# remote_glove_1_0_2021-01-08.net
KiCad netlist of a schematic drawn in EasyEDA
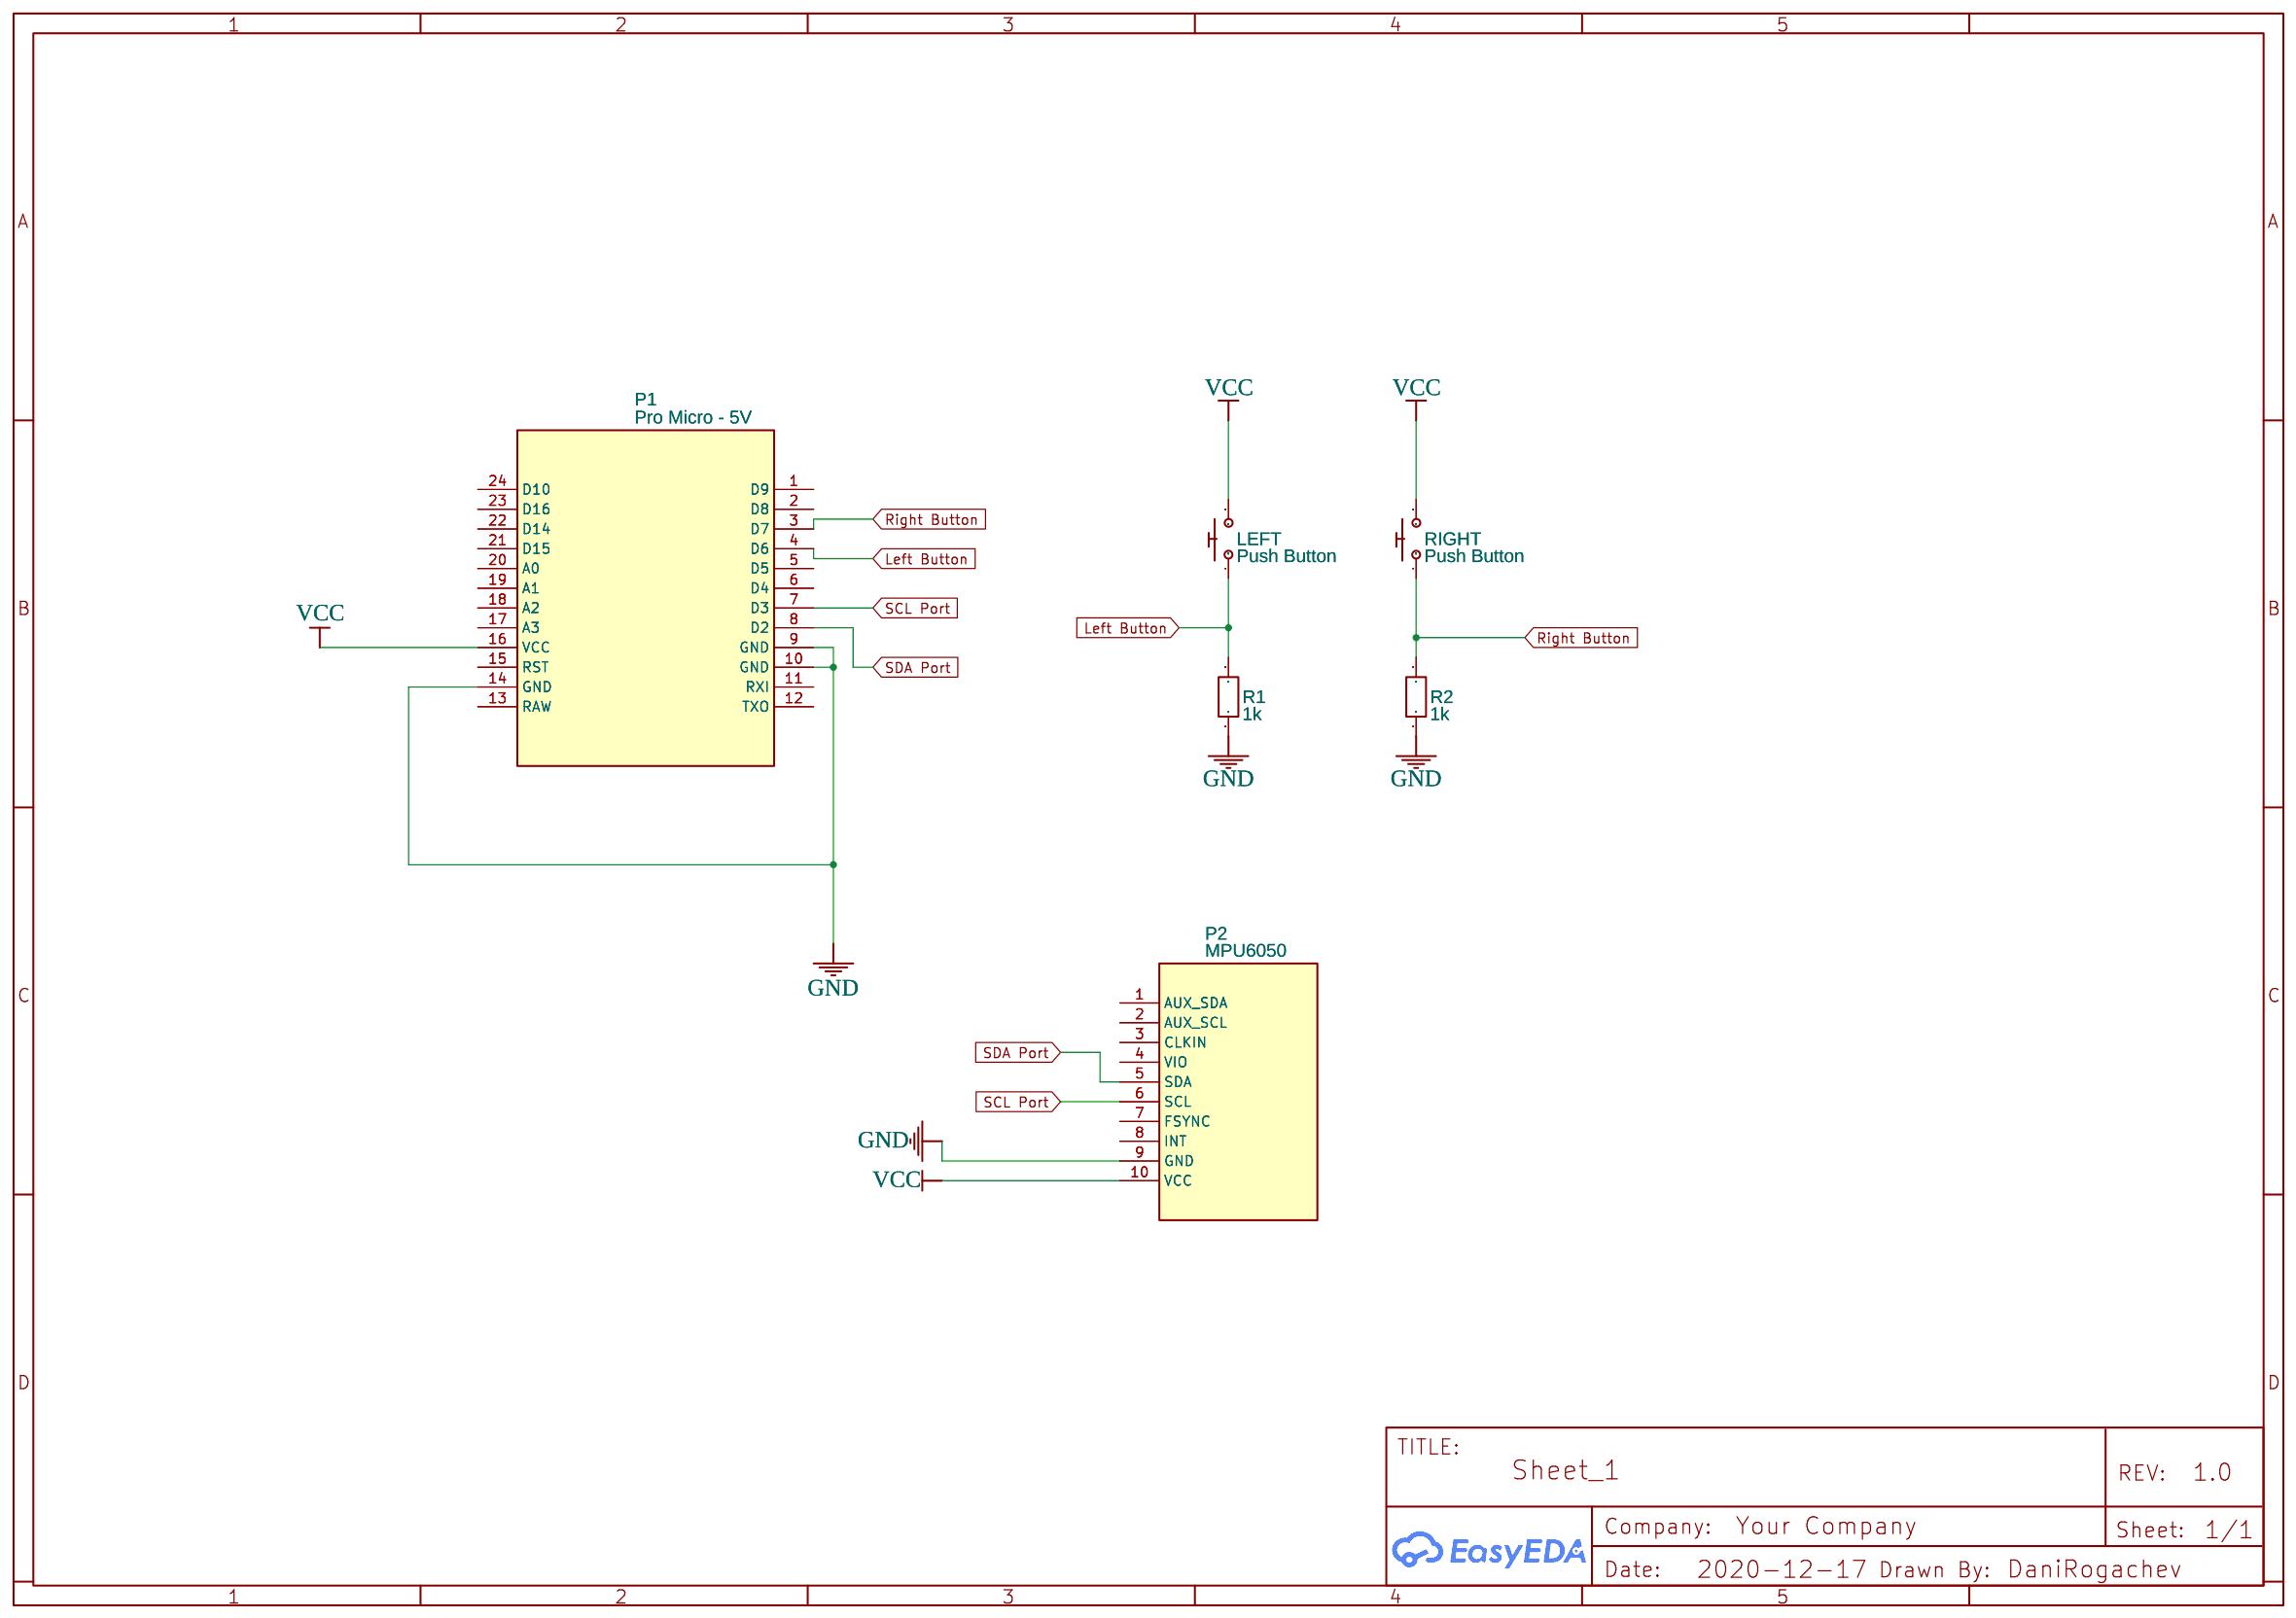
[diagram p0: schematic sheet]

(export (version "E")
  (design (tool "Eeschema 10.0.6"))
  (components
    (comp (ref "LEFT")
      (value "Push Button")
      (fields (field (name "BOM_Supplier Part") "COM-08720"))
      (libsource (lib "") (part "Push Button_1"))
    )
    (comp (ref "P1") (value "Pro Micro - 5V") (libsource (lib "") (part "Pro Micro - 5V")))
    (comp (ref "P2") (value "MPU6050") (libsource (lib "") (part "MPU6050")))
    (comp (ref "R1") (value "1k") (libsource (lib "") (part "R_0603_EU")))
    (comp (ref "R2") (value "1k") (libsource (lib "") (part "R_0603_EU")))
    (comp (ref "RIGHT")
      (value "Push Button")
      (fields (field (name "BOM_Supplier Part") "COM-08720"))
      (libsource (lib "") (part "Push Button"))
    )
  )
  (nets
    (net (code "1") (name "GND") (class "Default")
      (node (ref "P1") (pin "10") (pinfunction "GND_10") (pintype "unspecified"))
      (node (ref "P1") (pin "14") (pinfunction "GND_14") (pintype "unspecified"))
      (node (ref "P1") (pin "9") (pinfunction "GND_9") (pintype "unspecified"))
      (node (ref "P2") (pin "9") (pinfunction "GND_9") (pintype "unspecified"))
      (node (ref "R1") (pin "1") (pinfunction "1_1") (pintype "unspecified"))
      (node (ref "R2") (pin "1") (pinfunction "1_1") (pintype "unspecified"))
    )
    (net (code "2") (name "Left Button") (class "Default")
      (node (ref "LEFT") (pin "1") (pinfunction "P$1_1") (pintype "unspecified"))
      (node (ref "P1") (pin "4") (pinfunction "D6_4") (pintype "unspecified"))
      (node (ref "R1") (pin "2") (pinfunction "2_2") (pintype "unspecified"))
    )
    (net (code "3") (name "Right Button") (class "Default")
      (node (ref "P1") (pin "3") (pinfunction "D7_3") (pintype "unspecified"))
      (node (ref "R2") (pin "2") (pinfunction "2_2") (pintype "unspecified"))
      (node (ref "RIGHT") (pin "1") (pinfunction "P$1_1") (pintype "unspecified"))
    )
    (net (code "4") (name "SCL Port") (class "Default")
      (node (ref "P1") (pin "7") (pinfunction "D3_7") (pintype "unspecified"))
      (node (ref "P2") (pin "6") (pinfunction "SCL_6") (pintype "unspecified"))
    )
    (net (code "5") (name "SDA Port") (class "Default")
      (node (ref "P1") (pin "8") (pinfunction "D2_8") (pintype "unspecified"))
      (node (ref "P2") (pin "5") (pinfunction "SDA_5") (pintype "unspecified"))
    )
    (net (code "6") (name "VCC") (class "Default")
      (node (ref "LEFT") (pin "2") (pinfunction "P$2_2") (pintype "unspecified"))
      (node (ref "P1") (pin "16") (pinfunction "VCC_16") (pintype "unspecified"))
      (node (ref "P2") (pin "10") (pinfunction "VCC_10") (pintype "unspecified"))
      (node (ref "RIGHT") (pin "2") (pinfunction "P$2_2") (pintype "unspecified"))
    )
    (net (code "7") (name "unconnected-(P1-A0-Pad20)") (class "Default")
      (node (ref "P1") (pin "20") (pinfunction "A0_20") (pintype "unspecified"))
    )
    (net (code "8") (name "unconnected-(P1-A1-Pad19)") (class "Default")
      (node (ref "P1") (pin "19") (pinfunction "A1_19") (pintype "unspecified"))
    )
    (net (code "9") (name "unconnected-(P1-A2-Pad18)") (class "Default")
      (node (ref "P1") (pin "18") (pinfunction "A2_18") (pintype "unspecified"))
    )
    (net (code "10") (name "unconnected-(P1-A3-Pad17)") (class "Default")
      (node (ref "P1") (pin "17") (pinfunction "A3_17") (pintype "unspecified"))
    )
    (net (code "11") (name "unconnected-(P1-D4-Pad6)") (class "Default")
      (node (ref "P1") (pin "6") (pinfunction "D4_6") (pintype "unspecified"))
    )
    (net (code "12") (name "unconnected-(P1-D5-Pad5)") (class "Default")
      (node (ref "P1") (pin "5") (pinfunction "D5_5") (pintype "unspecified"))
    )
    (net (code "13") (name "unconnected-(P1-D8-Pad2)") (class "Default")
      (node (ref "P1") (pin "2") (pinfunction "D8_2") (pintype "unspecified"))
    )
    (net (code "14") (name "unconnected-(P1-D9-Pad1)") (class "Default")
      (node (ref "P1") (pin "1") (pinfunction "D9_1") (pintype "unspecified"))
    )
    (net (code "15") (name "unconnected-(P1-D10-Pad24)") (class "Default")
      (node (ref "P1") (pin "24") (pinfunction "D10_24") (pintype "unspecified"))
    )
    (net (code "16") (name "unconnected-(P1-D14-Pad22)") (class "Default")
      (node (ref "P1") (pin "22") (pinfunction "D14_22") (pintype "unspecified"))
    )
    (net (code "17") (name "unconnected-(P1-D15-Pad21)") (class "Default")
      (node (ref "P1") (pin "21") (pinfunction "D15_21") (pintype "unspecified"))
    )
    (net (code "18") (name "unconnected-(P1-D16-Pad23)") (class "Default")
      (node (ref "P1") (pin "23") (pinfunction "D16_23") (pintype "unspecified"))
    )
    (net (code "19") (name "unconnected-(P1-RAW-Pad13)") (class "Default")
      (node (ref "P1") (pin "13") (pinfunction "RAW_13") (pintype "unspecified"))
    )
    (net (code "20") (name "unconnected-(P1-RST-Pad15)") (class "Default")
      (node (ref "P1") (pin "15") (pinfunction "RST_15") (pintype "unspecified"))
    )
    (net (code "21") (name "unconnected-(P1-RXI-Pad11)") (class "Default")
      (node (ref "P1") (pin "11") (pinfunction "RXI_11") (pintype "unspecified"))
    )
    (net (code "22") (name "unconnected-(P1-TXO-Pad12)") (class "Default")
      (node (ref "P1") (pin "12") (pinfunction "TXO_12") (pintype "unspecified"))
    )
    (net (code "23") (name "unconnected-(P2-AUX_SCL-Pad2)") (class "Default")
      (node (ref "P2") (pin "2") (pinfunction "AUX_SCL_2") (pintype "unspecified"))
    )
    (net (code "24") (name "unconnected-(P2-AUX_SDA-Pad1)") (class "Default")
      (node (ref "P2") (pin "1") (pinfunction "AUX_SDA_1") (pintype "unspecified"))
    )
    (net (code "25") (name "unconnected-(P2-CLKIN-Pad3)") (class "Default")
      (node (ref "P2") (pin "3") (pinfunction "CLKIN_3") (pintype "unspecified"))
    )
    (net (code "26") (name "unconnected-(P2-FSYNC-Pad7)") (class "Default")
      (node (ref "P2") (pin "7") (pinfunction "FSYNC_7") (pintype "unspecified"))
    )
    (net (code "27") (name "unconnected-(P2-INT-Pad8)") (class "Default")
      (node (ref "P2") (pin "8") (pinfunction "INT_8") (pintype "unspecified"))
    )
    (net (code "28") (name "unconnected-(P2-VIO-Pad4)") (class "Default")
      (node (ref "P2") (pin "4") (pinfunction "VIO_4") (pintype "unspecified"))
    )
  )
)
